# relay_timer.net
KiCad netlist of a schematic drawn in EAGLE
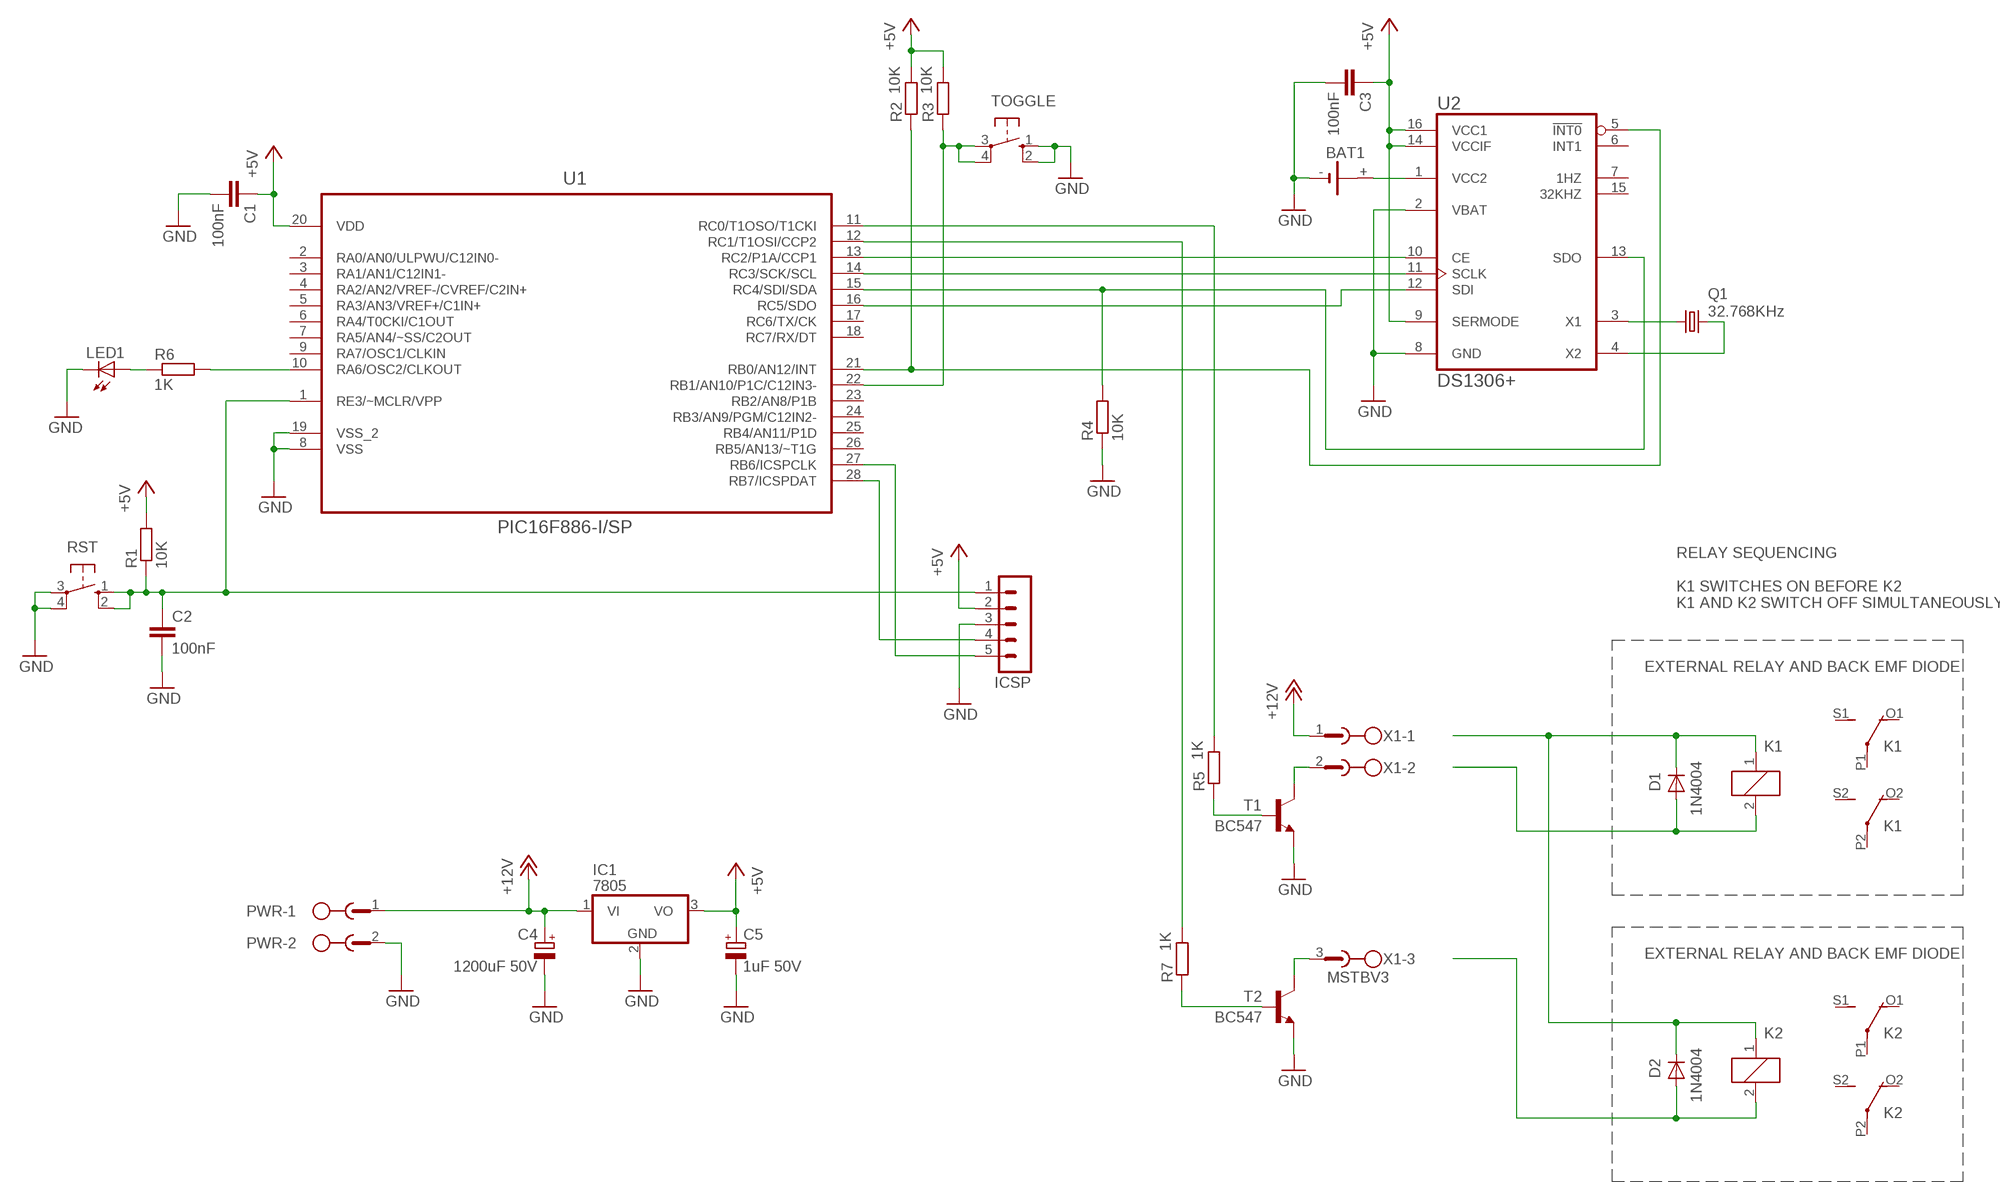
[diagram p0: schematic, sheet 1]

(export (version "E")
  (design (tool "Eeschema 10.0.6"))
  (components
    (comp (ref "BAT1")
      (value "CR2032H")
      (footprint "eagle-import:CR2032H")
      (libsource (lib "eagle-import") (part "CR2032H"))
    )
    (comp (ref "C1")
      (value "100nF")
      (footprint "eagle-import:C050-025X075")
      (libsource (lib "eagle-import") (part "C-EU050-025X075"))
    )
    (comp (ref "C2")
      (value "100nF")
      (footprint "eagle-import:C050-025X075")
      (libsource (lib "eagle-import") (part "C-EU050-025X075"))
    )
    (comp (ref "C3")
      (value "100nF")
      (footprint "eagle-import:C050-025X075")
      (libsource (lib "eagle-import") (part "C-EU050-025X075"))
    )
    (comp (ref "C4")
      (value "1200uF 50V")
      (footprint "eagle-import:E3,5-8")
      (libsource (lib "eagle-import") (part "CPOL-EUE3.5-8"))
    )
    (comp (ref "C5")
      (value "1uF 50V")
      (footprint "eagle-import:E2-5")
      (libsource (lib "eagle-import") (part "CPOL-EUE2-5"))
    )
    (comp (ref "D1")
      (value "1N4004")
      (footprint "eagle-import:DO41-10")
      (libsource (lib "eagle-import") (part "1N4004"))
    )
    (comp (ref "D2")
      (value "1N4004")
      (footprint "eagle-import:DO41-10")
      (libsource (lib "eagle-import") (part "1N4004"))
    )
    (comp (ref "IC1")
      (value "7805")
      (footprint "eagle-import:TO220V")
      (libsource (lib "eagle-import") (part "78TV05"))
    )
    (comp (ref "ICSP")
      (value "MA05-1")
      (footprint "eagle-import:MA05-1")
      (libsource (lib "eagle-import") (part "MA05-1"))
    )
    (comp (ref "K1")
      (value "G2R2")
      (footprint "eagle-import:G2R2")
      (fields (field (name "MF") "OMRON COMPONENTS USA") (field (name "MPN") "G2R-2-DC6"))
      (libsource (lib "eagle-import") (part "G2R2"))
    )
    (comp (ref "K2")
      (value "G2R2")
      (footprint "eagle-import:G2R2")
      (fields (field (name "MF") "OMRON COMPONENTS USA") (field (name "MPN") "G2R-2-DC6"))
      (libsource (lib "eagle-import") (part "G2R2"))
    )
    (comp (ref "LED1")
      (value "LED3MM")
      (footprint "eagle-import:LED3MM")
      (libsource (lib "eagle-import") (part "LED3MM"))
    )
    (comp (ref "PWR")
      (value "MSTBV2")
      (footprint "eagle-import:MSTBV2")
      (fields (field (name "MPN") "MSTBV 2,5/2-GF-5.08"))
      (libsource (lib "eagle-import") (part "MSTBV2"))
    )
    (comp (ref "Q1")
      (value "32.768KHz")
      (footprint "eagle-import:TC26H")
      (libsource (lib "eagle-import") (part "CRYSTALTC26H"))
    )
    (comp (ref "R1")
      (value "10K")
      (footprint "eagle-import:0207_10")
      (libsource (lib "eagle-import") (part "R-EU_0207/10"))
    )
    (comp (ref "R2")
      (value "10K")
      (footprint "eagle-import:0207_10")
      (libsource (lib "eagle-import") (part "R-EU_0207/10"))
    )
    (comp (ref "R3")
      (value "10K")
      (footprint "eagle-import:0207_10")
      (libsource (lib "eagle-import") (part "R-EU_0207/10"))
    )
    (comp (ref "R4")
      (value "10K")
      (footprint "eagle-import:0207_10")
      (libsource (lib "eagle-import") (part "R-EU_0207/10"))
    )
    (comp (ref "R5")
      (value "1K")
      (footprint "eagle-import:0207_10")
      (libsource (lib "eagle-import") (part "R-EU_0207/10"))
    )
    (comp (ref "R6")
      (value "1K")
      (footprint "eagle-import:0207_10")
      (libsource (lib "eagle-import") (part "R-EU_0207/10"))
    )
    (comp (ref "R7")
      (value "1K")
      (footprint "eagle-import:0207_10")
      (libsource (lib "eagle-import") (part "R-EU_0207/10"))
    )
    (comp (ref "RST")
      (value "10-XX")
      (footprint "eagle-import:B3F-10XX")
      (fields (field (name "MPN") "B3F-1000"))
      (libsource (lib "eagle-import") (part "10-XX"))
    )
    (comp (ref "T1")
      (value "BC547")
      (footprint "eagle-import:TO92-CBE")
      (libsource (lib "eagle-import") (part "-NPN-TO92-CBEBC547A"))
    )
    (comp (ref "T2")
      (value "BC547")
      (footprint "eagle-import:TO92-CBE")
      (libsource (lib "eagle-import") (part "-NPN-TO92-CBEBC547A"))
    )
    (comp (ref "TOGGLE")
      (value "10-XX")
      (footprint "eagle-import:B3F-10XX")
      (fields (field (name "MPN") "B3F-1000"))
      (libsource (lib "eagle-import") (part "10-XX"))
    )
    (comp (ref "U1")
      (value "PIC16F886-I/SP")
      (footprint "eagle-import:DIL28-3")
      (libsource (lib "eagle-import") (part "PIC16F886-I/SP"))
    )
    (comp (ref "U2")
      (value "DS1306+")
      (footprint "eagle-import:DIL16")
      (libsource (lib "eagle-import") (part "DS1306+"))
    )
    (comp (ref "X1")
      (value "MSTBV3")
      (footprint "eagle-import:MSTBV3")
      (fields (field (name "MPN") "MSTBV 2,5/3-GF-5.08"))
      (libsource (lib "eagle-import") (part "MSTBV3"))
    )
  )
  (nets
    (net (code "1") (name "+5V") (class "Default")
      (node (ref "C1") (pin "1") (pinfunction "1_1") (pintype "passive"))
      (node (ref "C3") (pin "1") (pinfunction "1_1") (pintype "passive"))
      (node (ref "C5") (pin "+") (pinfunction "+_+") (pintype "passive"))
      (node (ref "IC1") (pin "3") (pinfunction "VO_3") (pintype "passive"))
      (node (ref "ICSP") (pin "2") (pinfunction "2_2") (pintype "passive"))
      (node (ref "R1") (pin "2") (pinfunction "2_2") (pintype "passive"))
      (node (ref "R2") (pin "2") (pinfunction "2_2") (pintype "passive"))
      (node (ref "R3") (pin "2") (pinfunction "2_2") (pintype "passive"))
      (node (ref "U1") (pin "20") (pinfunction "VDD_20") (pintype "power_in"))
      (node (ref "U2") (pin "14") (pinfunction "VCCIF_14") (pintype "power_in"))
      (node (ref "U2") (pin "16") (pinfunction "VCC1_16") (pintype "power_in"))
      (node (ref "U2") (pin "9") (pinfunction "SERMODE_9") (pintype "input"))
    )
    (net (code "2") (name "+12V") (class "Default")
      (node (ref "C4") (pin "+") (pinfunction "+_+") (pintype "passive"))
      (node (ref "IC1") (pin "1") (pinfunction "VI_1") (pintype "input"))
      (node (ref "PWR") (pin "1") (pinfunction "1_1") (pintype "passive"))
      (node (ref "X1") (pin "1") (pinfunction "1_1") (pintype "passive"))
    )
    (net (code "3") (name "GND") (class "Default")
      (node (ref "BAT1") (pin "-") (pinfunction "-_-") (pintype "passive"))
      (node (ref "C1") (pin "2") (pinfunction "2_2") (pintype "passive"))
      (node (ref "C2") (pin "2") (pinfunction "2_2") (pintype "passive"))
      (node (ref "C3") (pin "2") (pinfunction "2_2") (pintype "passive"))
      (node (ref "C4") (pin "-") (pinfunction "-_-") (pintype "passive"))
      (node (ref "C5") (pin "-") (pinfunction "-_-") (pintype "passive"))
      (node (ref "IC1") (pin "2") (pinfunction "GND_2") (pintype "passive"))
      (node (ref "ICSP") (pin "3") (pinfunction "3_3") (pintype "passive"))
      (node (ref "LED1") (pin "K") (pinfunction "C_K") (pintype "passive"))
      (node (ref "PWR") (pin "2") (pinfunction "1_2") (pintype "passive"))
      (node (ref "R4") (pin "1") (pinfunction "1_1") (pintype "passive"))
      (node (ref "RST") (pin "3") (pinfunction "P_3") (pintype "passive"))
      (node (ref "RST") (pin "4") (pinfunction "P1_4") (pintype "passive"))
      (node (ref "T1") (pin "E") (pinfunction "E_E") (pintype "passive"))
      (node (ref "T2") (pin "E") (pinfunction "E_E") (pintype "passive"))
      (node (ref "TOGGLE") (pin "1") (pinfunction "S_1") (pintype "passive"))
      (node (ref "TOGGLE") (pin "2") (pinfunction "S1_2") (pintype "passive"))
      (node (ref "U1") (pin "19") (pinfunction "VSS_2_19") (pintype "passive"))
      (node (ref "U1") (pin "8") (pinfunction "VSS_8") (pintype "passive"))
      (node (ref "U2") (pin "2") (pinfunction "VBAT_2") (pintype "power_in"))
      (node (ref "U2") (pin "8") (pinfunction "GND_8") (pintype "power_in"))
    )
    (net (code "4") (name "Net-(D1-PadA)") (class "Default")
      (node (ref "D1") (pin "A") (pinfunction "A_A") (pintype "passive"))
      (node (ref "K1") (pin "2") (pinfunction "2_2") (pintype "passive"))
    )
    (net (code "5") (name "Net-(D1-PadC)") (class "Default")
      (node (ref "D1") (pin "C") (pinfunction "C_C") (pintype "passive"))
      (node (ref "D2") (pin "C") (pinfunction "C_C") (pintype "passive"))
      (node (ref "K1") (pin "1") (pinfunction "1_1") (pintype "passive"))
      (node (ref "K2") (pin "1") (pinfunction "1_1") (pintype "passive"))
    )
    (net (code "6") (name "Net-(D2-PadA)") (class "Default")
      (node (ref "D2") (pin "A") (pinfunction "A_A") (pintype "passive"))
      (node (ref "K2") (pin "2") (pinfunction "2_2") (pintype "passive"))
    )
    (net (code "7") (name "Net-(LED1-PadA)") (class "Default")
      (node (ref "LED1") (pin "A") (pinfunction "A_A") (pintype "passive"))
      (node (ref "R6") (pin "1") (pinfunction "1_1") (pintype "passive"))
    )
    (net (code "8") (name "Net-(R5-Pad1)") (class "Default")
      (node (ref "R5") (pin "1") (pinfunction "1_1") (pintype "passive"))
      (node (ref "T1") (pin "B") (pinfunction "B_B") (pintype "passive"))
    )
    (net (code "9") (name "Net-(R7-Pad1)") (class "Default")
      (node (ref "R7") (pin "1") (pinfunction "1_1") (pintype "passive"))
      (node (ref "T2") (pin "B") (pinfunction "B_B") (pintype "passive"))
    )
    (net (code "10") (name "Net-(RST-S)") (class "Default")
      (node (ref "C2") (pin "1") (pinfunction "1_1") (pintype "passive"))
      (node (ref "ICSP") (pin "1") (pinfunction "1_1") (pintype "passive"))
      (node (ref "R1") (pin "1") (pinfunction "1_1") (pintype "passive"))
      (node (ref "RST") (pin "1") (pinfunction "S_1") (pintype "passive"))
      (node (ref "RST") (pin "2") (pinfunction "S1_2") (pintype "passive"))
      (node (ref "U1") (pin "1") (pinfunction "RE3/~{MCLR/VPP}_1") (pintype "input"))
    )
    (net (code "11") (name "Net-(TOGGLE-P)") (class "Default")
      (node (ref "R3") (pin "1") (pinfunction "1_1") (pintype "passive"))
      (node (ref "TOGGLE") (pin "3") (pinfunction "P_3") (pintype "passive"))
      (node (ref "TOGGLE") (pin "4") (pinfunction "P1_4") (pintype "passive"))
      (node (ref "U1") (pin "22") (pinfunction "RB1/AN10/P1C/C12IN3-_22") (pintype "bidirectional"))
    )
    (net (code "12") (name "Net-(U1-RA6{slash}OSC2{slash}CLKOUT)") (class "Default")
      (node (ref "R6") (pin "2") (pinfunction "2_2") (pintype "passive"))
      (node (ref "U1") (pin "10") (pinfunction "RA6/OSC2/CLKOUT_10") (pintype "bidirectional"))
    )
    (net (code "13") (name "Net-(U1-RB0{slash}AN12{slash}INT)") (class "Default")
      (node (ref "R2") (pin "1") (pinfunction "1_1") (pintype "passive"))
      (node (ref "U1") (pin "21") (pinfunction "RB0/AN12/INT_21") (pintype "bidirectional"))
      (node (ref "U2") (pin "5") (pinfunction "~{INT0}_5") (pintype "open_collector"))
    )
    (net (code "14") (name "Net-(U1-RB6{slash}ICSPCLK)") (class "Default")
      (node (ref "ICSP") (pin "5") (pinfunction "5_5") (pintype "passive"))
      (node (ref "U1") (pin "27") (pinfunction "RB6/ICSPCLK_27") (pintype "bidirectional"))
    )
    (net (code "15") (name "Net-(U1-RB7{slash}ICSPDAT)") (class "Default")
      (node (ref "ICSP") (pin "4") (pinfunction "4_4") (pintype "passive"))
      (node (ref "U1") (pin "28") (pinfunction "RB7/ICSPDAT_28") (pintype "bidirectional"))
    )
    (net (code "16") (name "Net-(U1-RC0{slash}T1OSO{slash}T1CKI)") (class "Default")
      (node (ref "R5") (pin "2") (pinfunction "2_2") (pintype "passive"))
      (node (ref "U1") (pin "11") (pinfunction "RC0/T1OSO/T1CKI_11") (pintype "bidirectional"))
    )
    (net (code "17") (name "Net-(U1-RC1{slash}T1OSI{slash}CCP2)") (class "Default")
      (node (ref "R7") (pin "2") (pinfunction "2_2") (pintype "passive"))
      (node (ref "U1") (pin "12") (pinfunction "RC1/T1OSI/CCP2_12") (pintype "bidirectional"))
    )
    (net (code "18") (name "Net-(U1-RC2{slash}P1A{slash}CCP1)") (class "Default")
      (node (ref "U1") (pin "13") (pinfunction "RC2/P1A/CCP1_13") (pintype "bidirectional"))
      (node (ref "U2") (pin "10") (pinfunction "CE_10") (pintype "input"))
    )
    (net (code "19") (name "Net-(U1-RC3{slash}SCK{slash}SCL)") (class "Default")
      (node (ref "U1") (pin "14") (pinfunction "RC3/SCK/SCL_14") (pintype "bidirectional"))
      (node (ref "U2") (pin "11") (pinfunction "SCLK_11") (pintype "input"))
    )
    (net (code "20") (name "Net-(U1-RC4{slash}SDI{slash}SDA)") (class "Default")
      (node (ref "R4") (pin "2") (pinfunction "2_2") (pintype "passive"))
      (node (ref "U1") (pin "15") (pinfunction "RC4/SDI/SDA_15") (pintype "bidirectional"))
      (node (ref "U2") (pin "13") (pinfunction "SDO_13") (pintype "tri_state"))
    )
    (net (code "21") (name "Net-(U1-RC5{slash}SDO)") (class "Default")
      (node (ref "U1") (pin "16") (pinfunction "RC5/SDO_16") (pintype "bidirectional"))
      (node (ref "U2") (pin "12") (pinfunction "SDI_12") (pintype "input"))
    )
    (net (code "22") (name "Net-(U2-VCC2)") (class "Default")
      (node (ref "BAT1") (pin "+") (pinfunction "+_+") (pintype "passive"))
      (node (ref "U2") (pin "1") (pinfunction "VCC2_1") (pintype "power_in"))
    )
    (net (code "23") (name "Net-(U2-X1)") (class "Default")
      (node (ref "Q1") (pin "1") (pinfunction "1_1") (pintype "passive"))
      (node (ref "U2") (pin "3") (pinfunction "X1_3") (pintype "bidirectional"))
    )
    (net (code "24") (name "Net-(U2-X2)") (class "Default")
      (node (ref "Q1") (pin "2") (pinfunction "2_2") (pintype "passive"))
      (node (ref "U2") (pin "4") (pinfunction "X2_4") (pintype "bidirectional"))
    )
    (net (code "25") (name "Net-(X1B-1)") (class "Default")
      (node (ref "T1") (pin "C") (pinfunction "C_C") (pintype "passive"))
      (node (ref "X1") (pin "2") (pinfunction "1_2") (pintype "passive"))
    )
    (net (code "26") (name "Net-(X1C-1)") (class "Default")
      (node (ref "T2") (pin "C") (pinfunction "C_C") (pintype "passive"))
      (node (ref "X1") (pin "3") (pinfunction "1_3") (pintype "passive"))
    )
    (net (code "27") (name "unconnected-(BAT1-+-Pad+@1)") (class "Default")
      (node (ref "BAT1") (pin "+@1") (pinfunction "+_+@1") (pintype "passive"))
    )
    (net (code "28") (name "unconnected-(K1B-O-PadO1)") (class "Default")
      (node (ref "K1") (pin "O1") (pinfunction "O_O1") (pintype "passive"))
    )
    (net (code "29") (name "unconnected-(K1B-P-PadP1)") (class "Default")
      (node (ref "K1") (pin "P1") (pinfunction "P_P1") (pintype "passive"))
    )
    (net (code "30") (name "unconnected-(K1B-S-PadS1)") (class "Default")
      (node (ref "K1") (pin "S1") (pinfunction "S_S1") (pintype "passive"))
    )
    (net (code "31") (name "unconnected-(K1C-O-PadO2)") (class "Default")
      (node (ref "K1") (pin "O2") (pinfunction "O_O2") (pintype "passive"))
    )
    (net (code "32") (name "unconnected-(K1C-P-PadP2)") (class "Default")
      (node (ref "K1") (pin "P2") (pinfunction "P_P2") (pintype "passive"))
    )
    (net (code "33") (name "unconnected-(K1C-S-PadS2)") (class "Default")
      (node (ref "K1") (pin "S2") (pinfunction "S_S2") (pintype "passive"))
    )
    (net (code "34") (name "unconnected-(K2B-O-PadO1)") (class "Default")
      (node (ref "K2") (pin "O1") (pinfunction "O_O1") (pintype "passive"))
    )
    (net (code "35") (name "unconnected-(K2B-P-PadP1)") (class "Default")
      (node (ref "K2") (pin "P1") (pinfunction "P_P1") (pintype "passive"))
    )
    (net (code "36") (name "unconnected-(K2B-S-PadS1)") (class "Default")
      (node (ref "K2") (pin "S1") (pinfunction "S_S1") (pintype "passive"))
    )
    (net (code "37") (name "unconnected-(K2C-O-PadO2)") (class "Default")
      (node (ref "K2") (pin "O2") (pinfunction "O_O2") (pintype "passive"))
    )
    (net (code "38") (name "unconnected-(K2C-P-PadP2)") (class "Default")
      (node (ref "K2") (pin "P2") (pinfunction "P_P2") (pintype "passive"))
    )
    (net (code "39") (name "unconnected-(K2C-S-PadS2)") (class "Default")
      (node (ref "K2") (pin "S2") (pinfunction "S_S2") (pintype "passive"))
    )
    (net (code "40") (name "unconnected-(U1-RA0{slash}AN0{slash}ULPWU{slash}C12IN0--Pad2)") (class "Default")
      (node (ref "U1") (pin "2") (pinfunction "RA0/AN0/ULPWU/C12IN0-_2") (pintype "bidirectional"))
    )
    (net (code "41") (name "unconnected-(U1-RA1{slash}AN1{slash}C12IN1--Pad3)") (class "Default")
      (node (ref "U1") (pin "3") (pinfunction "RA1/AN1/C12IN1-_3") (pintype "bidirectional"))
    )
    (net (code "42") (name "unconnected-(U1-RA2{slash}AN2{slash}VREF-{slash}CVREF{slash}C2IN+-Pad4)") (class "Default")
      (node (ref "U1") (pin "4") (pinfunction "RA2/AN2/VREF-/CVREF/C2IN+_4") (pintype "bidirectional"))
    )
    (net (code "43") (name "unconnected-(U1-RA3{slash}AN3{slash}VREF+{slash}C1IN+-Pad5)") (class "Default")
      (node (ref "U1") (pin "5") (pinfunction "RA3/AN3/VREF+/C1IN+_5") (pintype "bidirectional"))
    )
    (net (code "44") (name "unconnected-(U1-RA4{slash}T0CKI{slash}C1OUT-Pad6)") (class "Default")
      (node (ref "U1") (pin "6") (pinfunction "RA4/T0CKI/C1OUT_6") (pintype "bidirectional"))
    )
    (net (code "45") (name "unconnected-(U1-RA5{slash}AN4{slash}~{SS{slash}C2OUT}-Pad7)") (class "Default")
      (node (ref "U1") (pin "7") (pinfunction "RA5/AN4/~{SS/C2OUT}_7") (pintype "bidirectional"))
    )
    (net (code "46") (name "unconnected-(U1-RA7{slash}OSC1{slash}CLKIN-Pad9)") (class "Default")
      (node (ref "U1") (pin "9") (pinfunction "RA7/OSC1/CLKIN_9") (pintype "bidirectional"))
    )
    (net (code "47") (name "unconnected-(U1-RB2{slash}AN8{slash}P1B-Pad23)") (class "Default")
      (node (ref "U1") (pin "23") (pinfunction "RB2/AN8/P1B_23") (pintype "bidirectional"))
    )
    (net (code "48") (name "unconnected-(U1-RB3{slash}AN9{slash}PGM{slash}C12IN2--Pad24)") (class "Default")
      (node (ref "U1") (pin "24") (pinfunction "RB3/AN9/PGM/C12IN2-_24") (pintype "bidirectional"))
    )
    (net (code "49") (name "unconnected-(U1-RB4{slash}AN11{slash}P1D-Pad25)") (class "Default")
      (node (ref "U1") (pin "25") (pinfunction "RB4/AN11/P1D_25") (pintype "bidirectional"))
    )
    (net (code "50") (name "unconnected-(U1-RB5{slash}AN13{slash}~{T1G}-Pad26)") (class "Default")
      (node (ref "U1") (pin "26") (pinfunction "RB5/AN13/~{T1G}_26") (pintype "bidirectional"))
    )
    (net (code "51") (name "unconnected-(U1-RC6{slash}TX{slash}CK-Pad17)") (class "Default")
      (node (ref "U1") (pin "17") (pinfunction "RC6/TX/CK_17") (pintype "bidirectional"))
    )
    (net (code "52") (name "unconnected-(U1-RC7{slash}RX{slash}DT-Pad18)") (class "Default")
      (node (ref "U1") (pin "18") (pinfunction "RC7/RX/DT_18") (pintype "bidirectional"))
    )
    (net (code "53") (name "unconnected-(U2-1HZ-Pad7)") (class "Default")
      (node (ref "U2") (pin "7") (pinfunction "1HZ_7") (pintype "output"))
    )
    (net (code "54") (name "unconnected-(U2-32KHZ-Pad15)") (class "Default")
      (node (ref "U2") (pin "15") (pinfunction "32KHZ_15") (pintype "output"))
    )
    (net (code "55") (name "unconnected-(U2-INT1-Pad6)") (class "Default")
      (node (ref "U2") (pin "6") (pinfunction "INT1_6") (pintype "output"))
    )
  )
)
